# LoRa.net
KiCad netlist of a schematic drawn in EAGLE
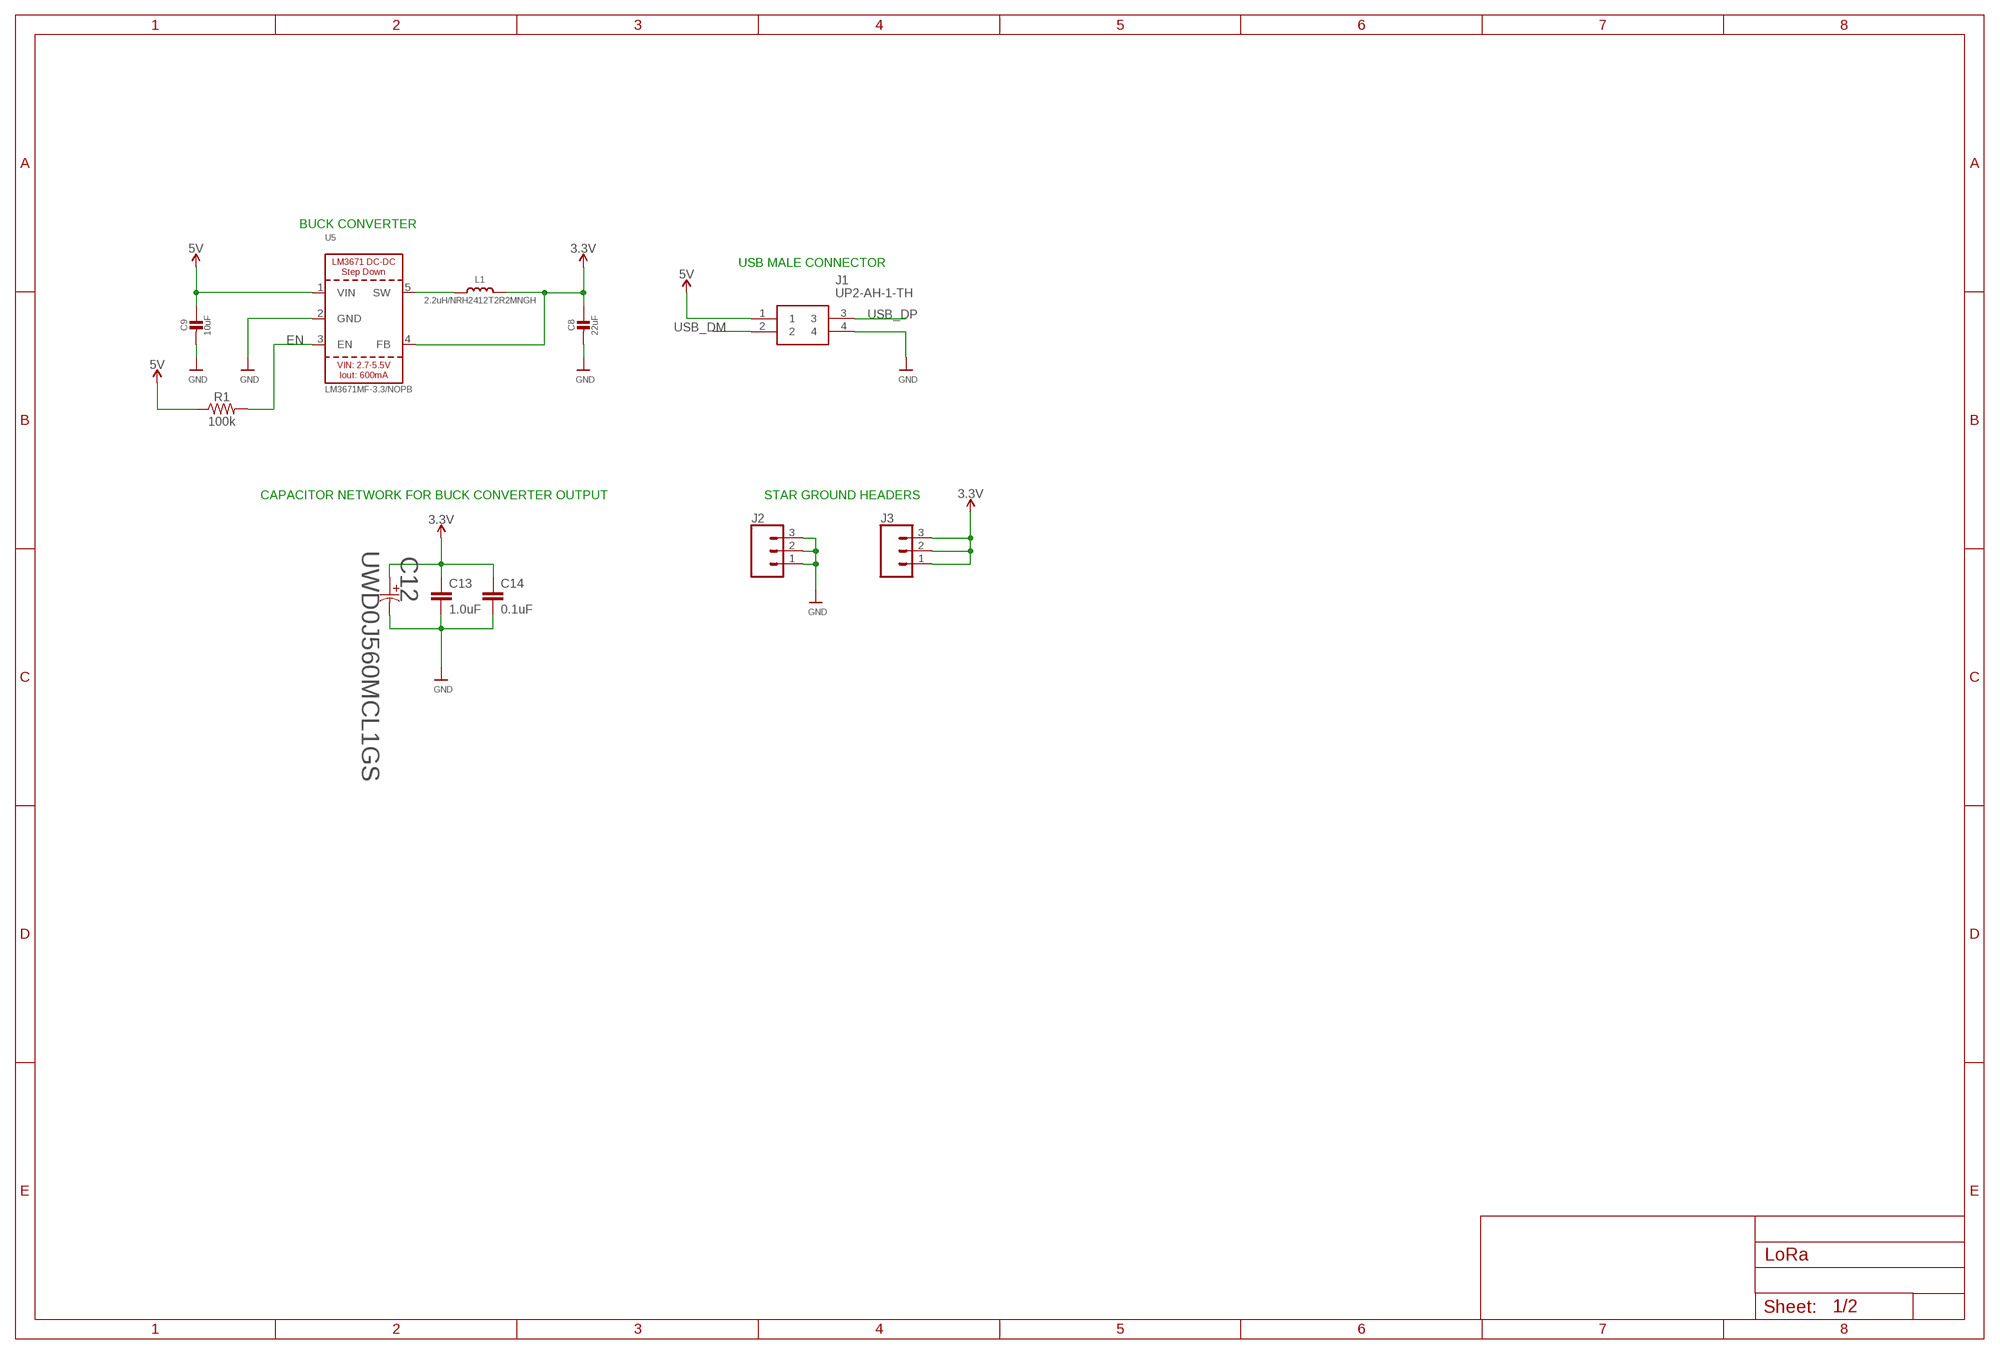
[diagram p0: schematic, sheet 1]
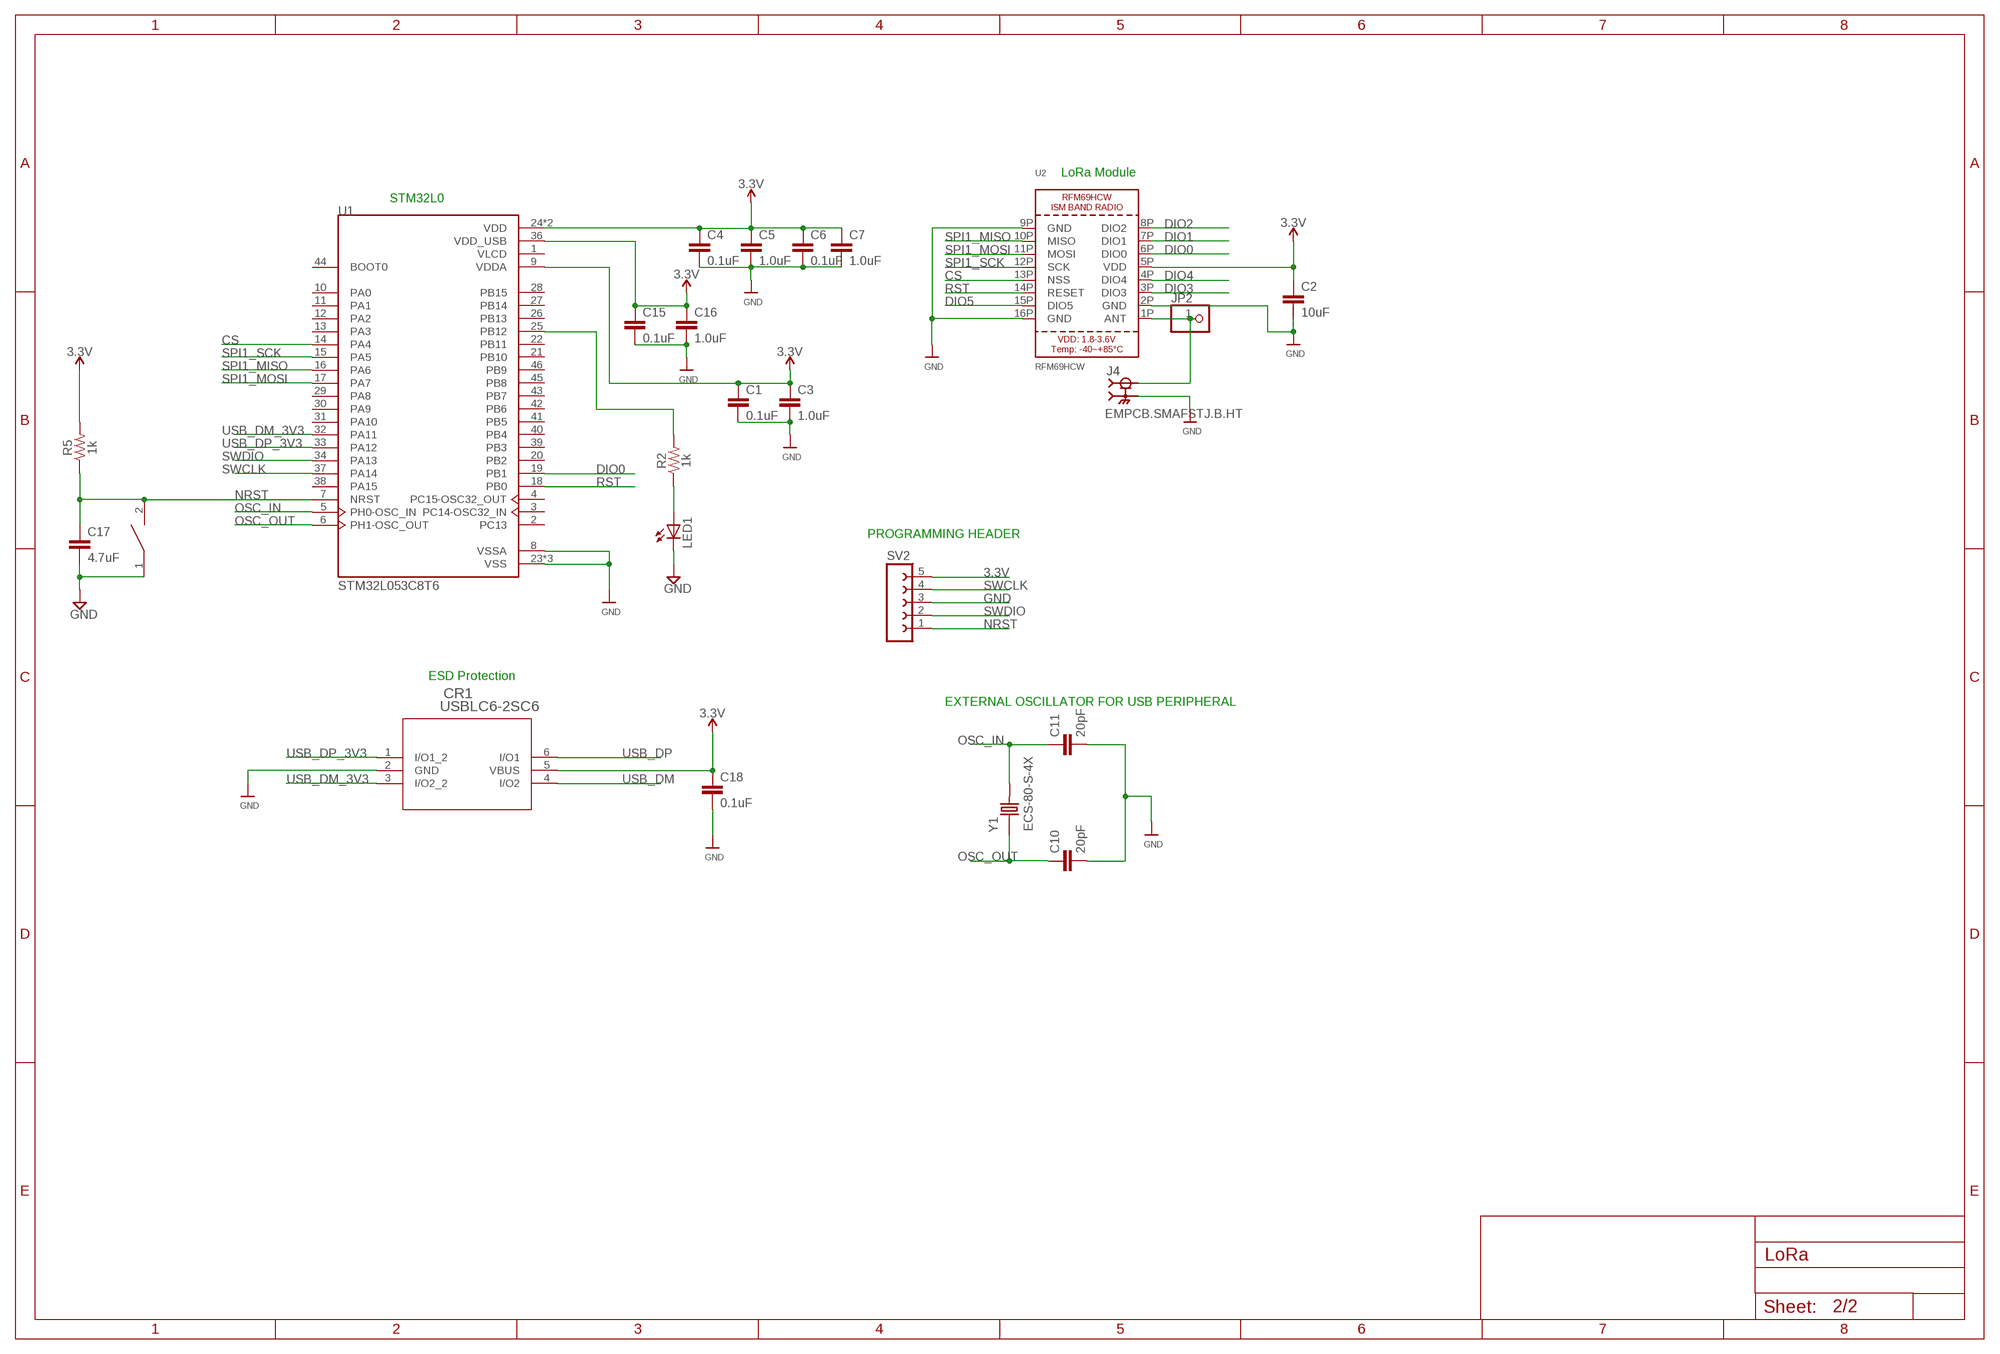
[diagram p1: schematic, sheet 2]

(export (version "E")
  (design (tool "Eeschema 10.0.6"))
  (components
    (comp (ref "C1")
      (value "0.1uF")
      (footprint "eagle-import:0603")
      (libsource (lib "eagle-import") (part "0.1UF-0603-25V-(+80/-20%)"))
    )
    (comp (ref "C2")
      (value "10uF")
      (footprint "eagle-import:0603")
      (libsource (lib "eagle-import") (part "10UF-0603-6.3V-20%"))
    )
    (comp (ref "C3")
      (value "1.0uF")
      (footprint "eagle-import:0603")
      (libsource (lib "eagle-import") (part "1.0UF-0603-16V-10%"))
    )
    (comp (ref "C4")
      (value "0.1uF")
      (footprint "eagle-import:0603")
      (libsource (lib "eagle-import") (part "0.1UF-0603-25V-(+80/-20%)"))
    )
    (comp (ref "C5")
      (value "1.0uF")
      (footprint "eagle-import:0603")
      (libsource (lib "eagle-import") (part "1.0UF-0603-16V-10%"))
    )
    (comp (ref "C6")
      (value "0.1uF")
      (footprint "eagle-import:0603")
      (libsource (lib "eagle-import") (part "0.1UF-0603-25V-(+80/-20%)"))
    )
    (comp (ref "C7")
      (value "1.0uF")
      (footprint "eagle-import:0603")
      (libsource (lib "eagle-import") (part "1.0UF-0603-16V-10%"))
    )
    (comp (ref "C10")
      (value "20pF")
      (footprint "eagle-import:0603")
      (libsource (lib "eagle-import") (part "4.7UF0603"))
    )
    (comp (ref "C11")
      (value "20pF")
      (footprint "eagle-import:0603")
      (libsource (lib "eagle-import") (part "4.7UF0603"))
    )
    (comp (ref "C15")
      (value "0.1uF")
      (footprint "eagle-import:0603")
      (libsource (lib "eagle-import") (part "0.1UF-0603-25V-(+80/-20%)"))
    )
    (comp (ref "C16")
      (value "1.0uF")
      (footprint "eagle-import:0603")
      (libsource (lib "eagle-import") (part "1.0UF-0603-16V-10%"))
    )
    (comp (ref "C17")
      (value "4.7uF")
      (footprint "eagle-import:0603")
      (libsource (lib "eagle-import") (part "4.7UF0603"))
    )
    (comp (ref "C18")
      (value "0.1uF")
      (footprint "eagle-import:0603")
      (libsource (lib "eagle-import") (part "0.1UF-0603-25V-(+80/-20%)"))
    )
    (comp (ref "CR1")
      (value "USBLC6-2SC6")
      (footprint "eagle-import:SOT23-6L")
      (libsource (lib "eagle-import") (part "USBLC6-2SC6"))
    )
    (comp (ref "J4")
      (value "EMPCB.SMAFSTJ.B.HT")
      (footprint "eagle-import:TAOGLAS_EMPCB.SMAFSTJ.B.HT")
      (fields (field (name "DIGI-KEY_PART_NUMBER") "931-1175-ND") (field (name "MF") "Taoglas Limited"))
      (libsource (lib "eagle-import") (part "EMPCB.SMAFSTJ.B.HT"))
    )
    (comp (ref "JP2")
      (value "HEADER-1X1ROUND")
      (footprint "eagle-import:1X01_ROUND")
      (libsource (lib "eagle-import") (part "HEADER-1X1ROUND"))
    )
    (comp (ref "LED1")
      (value "LEDCHIP-LED0805")
      (footprint "eagle-import:CHIP-LED0805")
      (fields (field (name "SPICEPREFIX") "L"))
      (libsource (lib "eagle-import") (part "LEDCHIP-LED0805"))
    )
    (comp (ref "R2")
      (value "1k")
      (footprint "eagle-import:0603")
      (libsource (lib "eagle-import") (part "1KOHM-0603-1/10W-1%"))
    )
    (comp (ref "R5")
      (value "1k")
      (footprint "eagle-import:0603")
      (libsource (lib "eagle-import") (part "1KOHM-0603-1/10W-1%"))
    )
    (comp (ref "RESET")
      (value "SWITCH")
      (footprint "eagle-import:SW_2512")
      (libsource (lib "eagle-import") (part "SWITCH"))
    )
    (comp (ref "SV2")
      (value "FE05-1")
      (footprint "eagle-import:FE05-1")
      (libsource (lib "eagle-import") (part "FE05-1"))
    )
    (comp (ref "U1")
      (value "STM32L053C8T6")
      (footprint "eagle-import:QFP50P900X900X160-48N")
      (fields (field (name "DIGI-KEY_PART_NUMBER") "497-14906-ND") (field (name "MF") "STMicroelectronics"))
      (libsource (lib "eagle-import") (part "STM32L053C8T6"))
    )
    (comp (ref "U2")
      (value "RFM69HCW")
      (footprint "eagle-import:RFMHCW_SMT")
      (libsource (lib "eagle-import") (part "RFM69HCW_SMT"))
    )
    (comp (ref "Y1")
      (value "ECS-80-S-4X")
      (footprint "eagle-import:XTAL_ECS-80-S-4X")
      (fields (field (name "DIGI-KEY_PART_NUMBER") "X1057-ND") (field (name "MF") "ECS International"))
      (libsource (lib "eagle-import") (part "ECS-80-S-4X"))
    )
    (comp (ref "C8")
      (value "22uF")
      (footprint "eagle-import:0805-NO")
      (libsource (lib "eagle-import") (part "CAP_CERAMIC0805-NOOUTLINE"))
    )
    (comp (ref "C9")
      (value "10uF")
      (footprint "eagle-import:0805-NO")
      (libsource (lib "eagle-import") (part "CAP_CERAMIC0805-NOOUTLINE"))
    )
    (comp (ref "C12")
      (value "UWD0J560MCL1GS")
      (footprint "eagle-import:PCAP_5X5.8-ELECT")
      (libsource (lib "eagle-import") (part "UWD0J560MCL1GS"))
    )
    (comp (ref "C13")
      (value "1.0uF")
      (footprint "eagle-import:0603")
      (libsource (lib "eagle-import") (part "1.0UF-0603-16V-10%"))
    )
    (comp (ref "C14")
      (value "0.1uF")
      (footprint "eagle-import:0603")
      (libsource (lib "eagle-import") (part "0.1UF-0603-25V-(+80/-20%)"))
    )
    (comp (ref "J1")
      (value "UP2-AH-1-TH")
      (footprint "eagle-import:UP2-AH-1-TH")
      (fields (field (name "MOUSER_PART_NUMBER") "490-UP2-AH-1-TH"))
      (libsource (lib "eagle-import") (part "UP2-AH-1-TH"))
    )
    (comp (ref "J2")
      (value "CONN_03")
      (footprint "eagle-import:1X03")
      (libsource (lib "eagle-import") (part "CONN_03"))
    )
    (comp (ref "J3")
      (value "CONN_03")
      (footprint "eagle-import:1X03")
      (libsource (lib "eagle-import") (part "CONN_03"))
    )
    (comp (ref "L1")
      (value "2.2uH/NRH2412T2R2MNGH")
      (footprint "eagle-import:INDUCTOR_TAIYOYUDEN_NRH2412T")
      (libsource (lib "eagle-import") (part "INDUCTORNRH2412T"))
    )
    (comp (ref "R1")
      (value "100k")
      (footprint "eagle-import:0603")
      (libsource (lib "eagle-import") (part "100KOHM-0603-1/10W-1%"))
    )
    (comp (ref "U5")
      (value "LM3671MF-3.3/NOPB")
      (footprint "eagle-import:SOT23-5")
      (libsource (lib "eagle-import") (part "VREG_LM3671"))
    )
  )
  (nets
    (net (code "1") (name "3.3V") (class "Default")
      (node (ref "C1") (pin "1") (pinfunction "1_1") (pintype "passive"))
      (node (ref "C12") (pin "1") (pinfunction "1_1") (pintype "passive"))
      (node (ref "C13") (pin "1") (pinfunction "1_1") (pintype "passive"))
      (node (ref "C14") (pin "1") (pinfunction "1_1") (pintype "passive"))
      (node (ref "C15") (pin "1") (pinfunction "1_1") (pintype "passive"))
      (node (ref "C16") (pin "1") (pinfunction "1_1") (pintype "passive"))
      (node (ref "C18") (pin "1") (pinfunction "1_1") (pintype "passive"))
      (node (ref "C2") (pin "1") (pinfunction "1_1") (pintype "passive"))
      (node (ref "C3") (pin "1") (pinfunction "1_1") (pintype "passive"))
      (node (ref "C4") (pin "1") (pinfunction "1_1") (pintype "passive"))
      (node (ref "C5") (pin "1") (pinfunction "1_1") (pintype "passive"))
      (node (ref "C6") (pin "1") (pinfunction "1_1") (pintype "passive"))
      (node (ref "C7") (pin "1") (pinfunction "1_1") (pintype "passive"))
      (node (ref "C8") (pin "1") (pinfunction "1_1") (pintype "passive"))
      (node (ref "CR1") (pin "5") (pinfunction "VBUS_5") (pintype "power_in"))
      (node (ref "J3") (pin "1") (pinfunction "1_1") (pintype "passive"))
      (node (ref "J3") (pin "2") (pinfunction "2_2") (pintype "passive"))
      (node (ref "J3") (pin "3") (pinfunction "3_3") (pintype "passive"))
      (node (ref "L1") (pin "2") (pinfunction "2_2") (pintype "passive"))
      (node (ref "R5") (pin "2") (pinfunction "2_2") (pintype "passive"))
      (node (ref "SV2") (pin "5") (pinfunction "5_5") (pintype "passive"))
      (node (ref "U1") (pin "24") (pinfunction "VDD_24") (pintype "bidirectional"))
      (node (ref "U1") (pin "36") (pinfunction "VDD_USB_36") (pintype "bidirectional"))
      (node (ref "U1") (pin "48") (pinfunction "VDD_48") (pintype "bidirectional"))
      (node (ref "U1") (pin "9") (pinfunction "VDDA_9") (pintype "bidirectional"))
      (node (ref "U2") (pin "5P") (pinfunction "VDD_5P") (pintype "power_in"))
      (node (ref "U5") (pin "4") (pinfunction "FB_4") (pintype "power_in"))
    )
    (net (code "2") (name "5V") (class "Default")
      (node (ref "C9") (pin "1") (pinfunction "1_1") (pintype "passive"))
      (node (ref "J1") (pin "1") (pinfunction "1_1") (pintype "bidirectional"))
      (node (ref "R1") (pin "1") (pinfunction "1_1") (pintype "passive"))
      (node (ref "U5") (pin "1") (pinfunction "VIN_1") (pintype "power_in"))
    )
    (net (code "3") (name "CS") (class "Default")
      (node (ref "U1") (pin "14") (pinfunction "PA4_14") (pintype "bidirectional"))
      (node (ref "U2") (pin "13P") (pinfunction "NSS_13P") (pintype "input"))
    )
    (net (code "4") (name "DIO0") (class "Default")
      (node (ref "U1") (pin "19") (pinfunction "PB1_19") (pintype "bidirectional"))
      (node (ref "U2") (pin "6P") (pinfunction "DIO0_6P") (pintype "bidirectional"))
    )
    (net (code "5") (name "DIO1") (class "Default")
      (node (ref "U2") (pin "7P") (pinfunction "DIO1_7P") (pintype "bidirectional"))
    )
    (net (code "6") (name "DIO2") (class "Default")
      (node (ref "U2") (pin "8P") (pinfunction "DIO2_8P") (pintype "bidirectional"))
    )
    (net (code "7") (name "DIO3") (class "Default")
      (node (ref "U2") (pin "3P") (pinfunction "DIO3_3P") (pintype "bidirectional"))
    )
    (net (code "8") (name "DIO4") (class "Default")
      (node (ref "U2") (pin "4P") (pinfunction "DIO4_4P") (pintype "bidirectional"))
    )
    (net (code "9") (name "DIO5") (class "Default")
      (node (ref "U2") (pin "15P") (pinfunction "DIO5_15P") (pintype "bidirectional"))
    )
    (net (code "10") (name "EN") (class "Default")
      (node (ref "R1") (pin "2") (pinfunction "2_2") (pintype "passive"))
      (node (ref "U5") (pin "3") (pinfunction "EN_3") (pintype "input"))
    )
    (net (code "11") (name "GND") (class "Default")
      (node (ref "C1") (pin "2") (pinfunction "2_2") (pintype "passive"))
      (node (ref "C10") (pin "2") (pinfunction "2_2") (pintype "passive"))
      (node (ref "C11") (pin "2") (pinfunction "2_2") (pintype "passive"))
      (node (ref "C12") (pin "2") (pinfunction "2_2") (pintype "passive"))
      (node (ref "C13") (pin "2") (pinfunction "2_2") (pintype "passive"))
      (node (ref "C14") (pin "2") (pinfunction "2_2") (pintype "passive"))
      (node (ref "C15") (pin "2") (pinfunction "2_2") (pintype "passive"))
      (node (ref "C16") (pin "2") (pinfunction "2_2") (pintype "passive"))
      (node (ref "C17") (pin "2") (pinfunction "2_2") (pintype "passive"))
      (node (ref "C18") (pin "2") (pinfunction "2_2") (pintype "passive"))
      (node (ref "C2") (pin "2") (pinfunction "2_2") (pintype "passive"))
      (node (ref "C3") (pin "2") (pinfunction "2_2") (pintype "passive"))
      (node (ref "C4") (pin "2") (pinfunction "2_2") (pintype "passive"))
      (node (ref "C5") (pin "2") (pinfunction "2_2") (pintype "passive"))
      (node (ref "C6") (pin "2") (pinfunction "2_2") (pintype "passive"))
      (node (ref "C7") (pin "2") (pinfunction "2_2") (pintype "passive"))
      (node (ref "C8") (pin "2") (pinfunction "2_2") (pintype "passive"))
      (node (ref "C9") (pin "2") (pinfunction "2_2") (pintype "passive"))
      (node (ref "CR1") (pin "2") (pinfunction "GND_2") (pintype "power_in"))
      (node (ref "J1") (pin "4") (pinfunction "4_4") (pintype "bidirectional"))
      (node (ref "J2") (pin "1") (pinfunction "1_1") (pintype "passive"))
      (node (ref "J2") (pin "2") (pinfunction "2_2") (pintype "passive"))
      (node (ref "J2") (pin "3") (pinfunction "3_3") (pintype "passive"))
      (node (ref "J4") (pin "SH1") (pinfunction "2_SH1") (pintype "passive"))
      (node (ref "J4") (pin "SH2") (pinfunction "2_SH2") (pintype "passive"))
      (node (ref "J4") (pin "SH3") (pinfunction "2_SH3") (pintype "passive"))
      (node (ref "J4") (pin "SH4") (pinfunction "2_SH4") (pintype "passive"))
      (node (ref "LED1") (pin "C") (pinfunction "C_C") (pintype "passive"))
      (node (ref "RESET") (pin "1") (pinfunction "P$1_1") (pintype "bidirectional"))
      (node (ref "SV2") (pin "3") (pinfunction "3_3") (pintype "passive"))
      (node (ref "U1") (pin "23") (pinfunction "VSS_23") (pintype "bidirectional"))
      (node (ref "U1") (pin "35") (pinfunction "VSS_35") (pintype "bidirectional"))
      (node (ref "U1") (pin "47") (pinfunction "VSS_47") (pintype "bidirectional"))
      (node (ref "U1") (pin "8") (pinfunction "VSSA_8") (pintype "bidirectional"))
      (node (ref "U2") (pin "16P") (pinfunction "GND_16P") (pintype "power_in"))
      (node (ref "U2") (pin "2P") (pinfunction "GND_2P") (pintype "power_in"))
      (node (ref "U2") (pin "9P") (pinfunction "GND_9P") (pintype "power_in"))
      (node (ref "U5") (pin "2") (pinfunction "GND_2") (pintype "power_in"))
    )
    (net (code "12") (name "NRST") (class "Default")
      (node (ref "C17") (pin "1") (pinfunction "1_1") (pintype "passive"))
      (node (ref "R5") (pin "1") (pinfunction "1_1") (pintype "passive"))
      (node (ref "RESET") (pin "2") (pinfunction "P$2_2") (pintype "bidirectional"))
      (node (ref "SV2") (pin "1") (pinfunction "1_1") (pintype "passive"))
      (node (ref "U1") (pin "7") (pinfunction "NRST_7") (pintype "bidirectional"))
    )
    (net (code "13") (name "Net-(LED1-PadA)") (class "Default")
      (node (ref "LED1") (pin "A") (pinfunction "A_A") (pintype "passive"))
      (node (ref "R2") (pin "1") (pinfunction "1_1") (pintype "passive"))
    )
    (net (code "14") (name "Net-(U1-PB12)") (class "Default")
      (node (ref "R2") (pin "2") (pinfunction "2_2") (pintype "passive"))
      (node (ref "U1") (pin "25") (pinfunction "PB12_25") (pintype "bidirectional"))
    )
    (net (code "15") (name "Net-(U2-ANT)") (class "Default")
      (node (ref "J4") (pin "1") (pinfunction "1_1") (pintype "passive"))
      (node (ref "JP2") (pin "1") (pinfunction "1_1") (pintype "passive"))
      (node (ref "U2") (pin "1P") (pinfunction "ANT_1P") (pintype "bidirectional"))
    )
    (net (code "16") (name "Net-(U5-SW)") (class "Default")
      (node (ref "L1") (pin "1") (pinfunction "1_1") (pintype "passive"))
      (node (ref "U5") (pin "5") (pinfunction "SW_5") (pintype "output"))
    )
    (net (code "17") (name "OSC_IN") (class "Default")
      (node (ref "C11") (pin "1") (pinfunction "1_1") (pintype "passive"))
      (node (ref "U1") (pin "5") (pinfunction "PH0-OSC_IN_5") (pintype "bidirectional"))
      (node (ref "Y1") (pin "2") (pinfunction "2_2") (pintype "passive"))
    )
    (net (code "18") (name "OSC_OUT") (class "Default")
      (node (ref "C10") (pin "1") (pinfunction "1_1") (pintype "passive"))
      (node (ref "U1") (pin "6") (pinfunction "PH1-OSC_OUT_6") (pintype "bidirectional"))
      (node (ref "Y1") (pin "1") (pinfunction "1_1") (pintype "passive"))
    )
    (net (code "19") (name "RST") (class "Default")
      (node (ref "U1") (pin "18") (pinfunction "PB0_18") (pintype "bidirectional"))
      (node (ref "U2") (pin "14P") (pinfunction "RESET_14P") (pintype "input"))
    )
    (net (code "20") (name "SPI1_MISO") (class "Default")
      (node (ref "U1") (pin "16") (pinfunction "PA6_16") (pintype "bidirectional"))
      (node (ref "U2") (pin "10P") (pinfunction "MISO_10P") (pintype "output"))
    )
    (net (code "21") (name "SPI1_MOSI") (class "Default")
      (node (ref "U1") (pin "17") (pinfunction "PA7_17") (pintype "bidirectional"))
      (node (ref "U2") (pin "11P") (pinfunction "MOSI_11P") (pintype "input"))
    )
    (net (code "22") (name "SPI1_SCK") (class "Default")
      (node (ref "U1") (pin "15") (pinfunction "PA5_15") (pintype "bidirectional"))
      (node (ref "U2") (pin "12P") (pinfunction "SCK_12P") (pintype "input"))
    )
    (net (code "23") (name "SWCLK") (class "Default")
      (node (ref "SV2") (pin "4") (pinfunction "4_4") (pintype "passive"))
      (node (ref "U1") (pin "37") (pinfunction "PA14_37") (pintype "bidirectional"))
    )
    (net (code "24") (name "SWDIO") (class "Default")
      (node (ref "SV2") (pin "2") (pinfunction "2_2") (pintype "passive"))
      (node (ref "U1") (pin "34") (pinfunction "PA13_34") (pintype "bidirectional"))
    )
    (net (code "25") (name "USB_DM") (class "Default")
      (node (ref "CR1") (pin "4") (pinfunction "I/O2_4") (pintype "bidirectional"))
      (node (ref "J1") (pin "2") (pinfunction "2_2") (pintype "bidirectional"))
    )
    (net (code "26") (name "USB_DM_3V3") (class "Default")
      (node (ref "CR1") (pin "3") (pinfunction "I/O2_2_3") (pintype "bidirectional"))
      (node (ref "U1") (pin "32") (pinfunction "PA11_32") (pintype "bidirectional"))
    )
    (net (code "27") (name "USB_DP") (class "Default")
      (node (ref "CR1") (pin "6") (pinfunction "I/O1_6") (pintype "bidirectional"))
      (node (ref "J1") (pin "3") (pinfunction "3_3") (pintype "bidirectional"))
    )
    (net (code "28") (name "USB_DP_3V3") (class "Default")
      (node (ref "CR1") (pin "1") (pinfunction "I/O1_2_1") (pintype "bidirectional"))
      (node (ref "U1") (pin "33") (pinfunction "PA12_33") (pintype "bidirectional"))
    )
    (net (code "29") (name "unconnected-(U1-BOOT0-Pad44)") (class "Default")
      (node (ref "U1") (pin "44") (pinfunction "BOOT0_44") (pintype "input"))
    )
    (net (code "30") (name "unconnected-(U1-PA0-Pad10)") (class "Default")
      (node (ref "U1") (pin "10") (pinfunction "PA0_10") (pintype "bidirectional"))
    )
    (net (code "31") (name "unconnected-(U1-PA1-Pad11)") (class "Default")
      (node (ref "U1") (pin "11") (pinfunction "PA1_11") (pintype "bidirectional"))
    )
    (net (code "32") (name "unconnected-(U1-PA2-Pad12)") (class "Default")
      (node (ref "U1") (pin "12") (pinfunction "PA2_12") (pintype "bidirectional"))
    )
    (net (code "33") (name "unconnected-(U1-PA3-Pad13)") (class "Default")
      (node (ref "U1") (pin "13") (pinfunction "PA3_13") (pintype "bidirectional"))
    )
    (net (code "34") (name "unconnected-(U1-PA8-Pad29)") (class "Default")
      (node (ref "U1") (pin "29") (pinfunction "PA8_29") (pintype "bidirectional"))
    )
    (net (code "35") (name "unconnected-(U1-PA9-Pad30)") (class "Default")
      (node (ref "U1") (pin "30") (pinfunction "PA9_30") (pintype "bidirectional"))
    )
    (net (code "36") (name "unconnected-(U1-PA10-Pad31)") (class "Default")
      (node (ref "U1") (pin "31") (pinfunction "PA10_31") (pintype "bidirectional"))
    )
    (net (code "37") (name "unconnected-(U1-PA15-Pad38)") (class "Default")
      (node (ref "U1") (pin "38") (pinfunction "PA15_38") (pintype "bidirectional"))
    )
    (net (code "38") (name "unconnected-(U1-PB2-Pad20)") (class "Default")
      (node (ref "U1") (pin "20") (pinfunction "PB2_20") (pintype "bidirectional"))
    )
    (net (code "39") (name "unconnected-(U1-PB3-Pad39)") (class "Default")
      (node (ref "U1") (pin "39") (pinfunction "PB3_39") (pintype "bidirectional"))
    )
    (net (code "40") (name "unconnected-(U1-PB4-Pad40)") (class "Default")
      (node (ref "U1") (pin "40") (pinfunction "PB4_40") (pintype "bidirectional"))
    )
    (net (code "41") (name "unconnected-(U1-PB5-Pad41)") (class "Default")
      (node (ref "U1") (pin "41") (pinfunction "PB5_41") (pintype "bidirectional"))
    )
    (net (code "42") (name "unconnected-(U1-PB6-Pad42)") (class "Default")
      (node (ref "U1") (pin "42") (pinfunction "PB6_42") (pintype "bidirectional"))
    )
    (net (code "43") (name "unconnected-(U1-PB7-Pad43)") (class "Default")
      (node (ref "U1") (pin "43") (pinfunction "PB7_43") (pintype "bidirectional"))
    )
    (net (code "44") (name "unconnected-(U1-PB8-Pad45)") (class "Default")
      (node (ref "U1") (pin "45") (pinfunction "PB8_45") (pintype "bidirectional"))
    )
    (net (code "45") (name "unconnected-(U1-PB9-Pad46)") (class "Default")
      (node (ref "U1") (pin "46") (pinfunction "PB9_46") (pintype "bidirectional"))
    )
    (net (code "46") (name "unconnected-(U1-PB10-Pad21)") (class "Default")
      (node (ref "U1") (pin "21") (pinfunction "PB10_21") (pintype "bidirectional"))
    )
    (net (code "47") (name "unconnected-(U1-PB11-Pad22)") (class "Default")
      (node (ref "U1") (pin "22") (pinfunction "PB11_22") (pintype "bidirectional"))
    )
    (net (code "48") (name "unconnected-(U1-PB13-Pad26)") (class "Default")
      (node (ref "U1") (pin "26") (pinfunction "PB13_26") (pintype "bidirectional"))
    )
    (net (code "49") (name "unconnected-(U1-PB14-Pad27)") (class "Default")
      (node (ref "U1") (pin "27") (pinfunction "PB14_27") (pintype "bidirectional"))
    )
    (net (code "50") (name "unconnected-(U1-PB15-Pad28)") (class "Default")
      (node (ref "U1") (pin "28") (pinfunction "PB15_28") (pintype "bidirectional"))
    )
    (net (code "51") (name "unconnected-(U1-PC13-Pad2)") (class "Default")
      (node (ref "U1") (pin "2") (pinfunction "PC13_2") (pintype "bidirectional"))
    )
    (net (code "52") (name "unconnected-(U1-PC14-OSC32_IN-Pad3)") (class "Default")
      (node (ref "U1") (pin "3") (pinfunction "PC14-OSC32_IN_3") (pintype "bidirectional"))
    )
    (net (code "53") (name "unconnected-(U1-PC15-OSC32_OUT-Pad4)") (class "Default")
      (node (ref "U1") (pin "4") (pinfunction "PC15-OSC32_OUT_4") (pintype "bidirectional"))
    )
    (net (code "54") (name "unconnected-(U1-VLCD-Pad1)") (class "Default")
      (node (ref "U1") (pin "1") (pinfunction "VLCD_1") (pintype "bidirectional"))
    )
  )
)
